# GL3520_4_Ports.net
KiCad netlist of a schematic drawn in Altium Designer
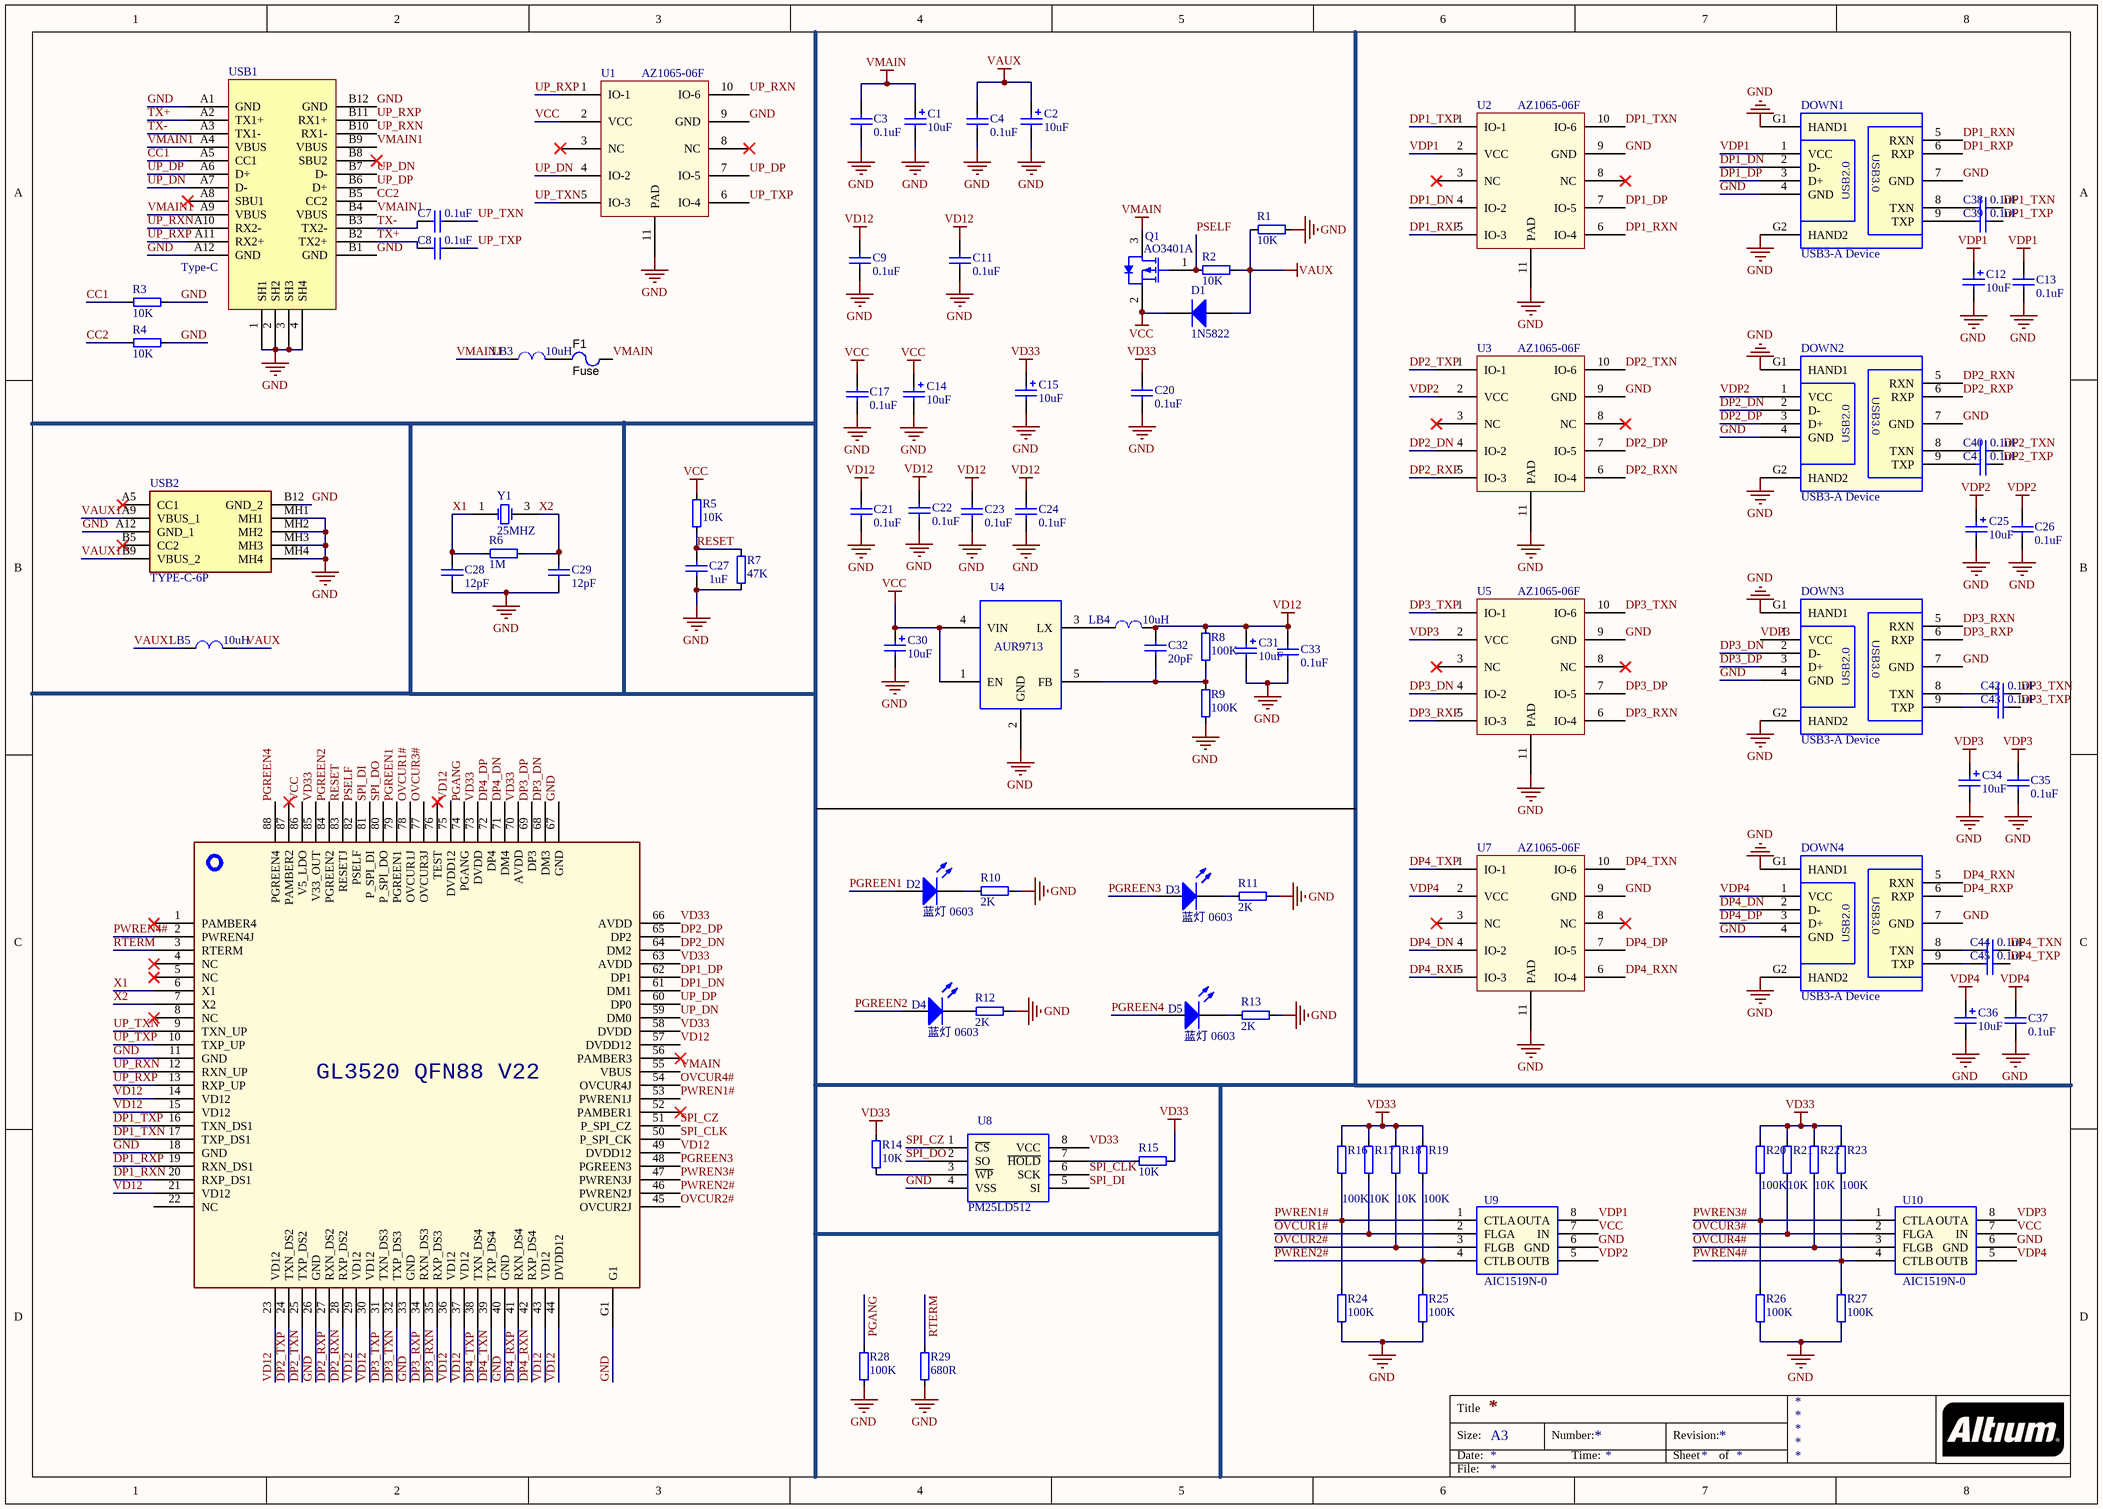
[diagram p0: GL3520 4 Ports.SchDoc]

(export (version "E")
  (design (tool "Eeschema 10.0.6"))
  (components
    (comp (ref "C1")
      (value "10uF")
      (footprint "CASE-A_3216")
      (description "钽电容1206")
      (libsource (lib "嘉立创") (part "3216 10uF (106) 10% 16V"))
    )
    (comp (ref "C2")
      (value "10uF")
      (footprint "CASE-A_3216")
      (description "钽电容1206")
      (libsource (lib "嘉立创") (part "3216 10uF (106) 10% 16V"))
    )
    (comp (ref "C3")
      (value "0.1uF")
      (footprint "C 0603_L")
      (description "贴片电容")
      (libsource (lib "嘉立创") (part "0603 2.2uF (225) 10% 16V"))
    )
    (comp (ref "C4")
      (value "0.1uF")
      (footprint "C 0603_L")
      (description "贴片电容")
      (libsource (lib "嘉立创") (part "0603 2.2uF (225) 10% 16V"))
    )
    (comp (ref "C7")
      (value "0.1uF")
      (footprint "C 0603_L")
      (description "贴片电容")
      (libsource (lib "嘉立创") (part "0603 2.2uF (225) 10% 16V"))
    )
    (comp (ref "C8")
      (value "0.1uF")
      (footprint "C 0603_L")
      (description "贴片电容")
      (libsource (lib "嘉立创") (part "0603 2.2uF (225) 10% 16V"))
    )
    (comp (ref "C9")
      (value "0.1uF")
      (footprint "C 0603_L")
      (description "贴片电容")
      (libsource (lib "嘉立创") (part "0603 2.2uF (225) 10% 16V"))
    )
    (comp (ref "C11")
      (value "0.1uF")
      (footprint "C 0603_L")
      (description "贴片电容")
      (libsource (lib "嘉立创") (part "0603 2.2uF (225) 10% 16V"))
    )
    (comp (ref "C12")
      (value "10uF")
      (footprint "CASE-A_3216")
      (description "钽电容")
      (libsource (lib "嘉立创") (part "3216 10uF (106) 10% 16V"))
    )
    (comp (ref "C13")
      (value "0.1uF")
      (footprint "C 0603_L")
      (description "贴片电容")
      (libsource (lib "嘉立创") (part "0603 2.2uF (225) 10% 16V"))
    )
    (comp (ref "C14")
      (value "10uF")
      (footprint "CASE-A_3216")
      (description "钽电容1206")
      (libsource (lib "嘉立创") (part "3216 10uF (106) 10% 16V"))
    )
    (comp (ref "C15")
      (value "10uF")
      (footprint "CASE-A_3216")
      (description "钽电容1206")
      (libsource (lib "嘉立创") (part "3216 10uF (106) 10% 16V"))
    )
    (comp (ref "C17")
      (value "0.1uF")
      (footprint "C 0603_L")
      (description "贴片电容")
      (libsource (lib "嘉立创") (part "0603 2.2uF (225) 10% 16V"))
    )
    (comp (ref "C20")
      (value "0.1uF")
      (footprint "C 0603_L")
      (description "贴片电容")
      (libsource (lib "嘉立创") (part "0603 2.2uF (225) 10% 16V"))
    )
    (comp (ref "C21")
      (value "0.1uF")
      (footprint "C 0603_L")
      (description "贴片电容")
      (libsource (lib "嘉立创") (part "0603 2.2uF (225) 10% 16V"))
    )
    (comp (ref "C22")
      (value "0.1uF")
      (footprint "C 0603_L")
      (description "贴片电容")
      (libsource (lib "嘉立创") (part "0603 2.2uF (225) 10% 16V"))
    )
    (comp (ref "C23")
      (value "0.1uF")
      (footprint "C 0603_L")
      (description "贴片电容")
      (libsource (lib "嘉立创") (part "0603 2.2uF (225) 10% 16V"))
    )
    (comp (ref "C24")
      (value "0.1uF")
      (footprint "C 0603_L")
      (description "贴片电容")
      (libsource (lib "嘉立创") (part "0603 2.2uF (225) 10% 16V"))
    )
    (comp (ref "C25")
      (value "10uF")
      (footprint "CASE-A_3216")
      (description "钽电容")
      (libsource (lib "嘉立创") (part "3216 10uF (106) 10% 16V"))
    )
    (comp (ref "C26")
      (value "0.1uF")
      (footprint "C 0603_L")
      (description "贴片电容")
      (libsource (lib "嘉立创") (part "0603 2.2uF (225) 10% 16V"))
    )
    (comp (ref "C27")
      (value "1uF")
      (footprint "C 0603_L")
      (description "贴片电容")
      (libsource (lib "嘉立创") (part "0603 2.2uF (225) 10% 16V"))
    )
    (comp (ref "C28")
      (value "12pF")
      (footprint "C 0603_L")
      (description "贴片电容")
      (libsource (lib "嘉立创") (part "0603 2.2uF (225) 10% 16V"))
    )
    (comp (ref "C29")
      (value "12pF")
      (footprint "C 0603_L")
      (description "贴片电容")
      (libsource (lib "嘉立创") (part "0603 2.2uF (225) 10% 16V"))
    )
    (comp (ref "C30")
      (value "10uF")
      (footprint "CASE-A_3216")
      (description "钽电容")
      (libsource (lib "嘉立创") (part "3216 10uF (106) 10% 16V"))
    )
    (comp (ref "C31")
      (value "10uF")
      (footprint "CASE-A_3216")
      (description "钽电容")
      (libsource (lib "嘉立创") (part "3216 10uF (106) 10% 16V"))
    )
    (comp (ref "C32")
      (value "20pF")
      (footprint "C 0603_L")
      (description "贴片电容")
      (libsource (lib "嘉立创") (part "0603 2.2uF (225) 10% 16V"))
    )
    (comp (ref "C33")
      (value "0.1uF")
      (footprint "C 0603_L")
      (description "贴片电容")
      (libsource (lib "嘉立创") (part "0603 2.2uF (225) 10% 16V"))
    )
    (comp (ref "C34")
      (value "10uF")
      (footprint "CASE-A_3216")
      (description "钽电容")
      (libsource (lib "嘉立创") (part "3216 10uF (106) 10% 16V"))
    )
    (comp (ref "C35")
      (value "0.1uF")
      (footprint "C 0603_L")
      (description "贴片电容")
      (libsource (lib "嘉立创") (part "0603 2.2uF (225) 10% 16V"))
    )
    (comp (ref "C36")
      (value "10uF")
      (footprint "CASE-A_3216")
      (description "钽电容")
      (libsource (lib "嘉立创") (part "3216 10uF (106) 10% 16V"))
    )
    (comp (ref "C37")
      (value "0.1uF")
      (footprint "C 0603_L")
      (description "贴片电容")
      (libsource (lib "嘉立创") (part "0603 2.2uF (225) 10% 16V"))
    )
    (comp (ref "C38")
      (value "0.1uF")
      (footprint "C 0603_L")
      (description "贴片电容")
      (libsource (lib "嘉立创") (part "0603 2.2uF (225) 10% 16V"))
    )
    (comp (ref "C39")
      (value "0.1uF")
      (footprint "C 0603_L")
      (description "贴片电容")
      (libsource (lib "嘉立创") (part "0603 2.2uF (225) 10% 16V"))
    )
    (comp (ref "C40")
      (value "0.1uF")
      (footprint "C 0603_L")
      (description "贴片电容")
      (libsource (lib "嘉立创") (part "0603 2.2uF (225) 10% 16V"))
    )
    (comp (ref "C41")
      (value "0.1uF")
      (footprint "C 0603_L")
      (description "贴片电容")
      (libsource (lib "嘉立创") (part "0603 2.2uF (225) 10% 16V"))
    )
    (comp (ref "C42")
      (value "0.1uF")
      (footprint "C 0603_L")
      (description "贴片电容")
      (libsource (lib "嘉立创") (part "0603 2.2uF (225) 10% 16V"))
    )
    (comp (ref "C43")
      (value "0.1uF")
      (footprint "C 0603_L")
      (description "贴片电容")
      (libsource (lib "嘉立创") (part "0603 2.2uF (225) 10% 16V"))
    )
    (comp (ref "C44")
      (value "0.1uF")
      (footprint "C 0603_L")
      (description "贴片电容")
      (libsource (lib "嘉立创") (part "0603 2.2uF (225) 10% 16V"))
    )
    (comp (ref "C45")
      (value "0.1uF")
      (footprint "C 0603_L")
      (description "贴片电容")
      (libsource (lib "嘉立创") (part "0603 2.2uF (225) 10% 16V"))
    )
    (comp (ref "D1")
      (value "1N5822")
      (footprint "SMA")
      (description "3 Amp General Purpose Rectifier")
      (fields (field (name "PUBLISHER") "Altium Limited"))
      (libsource (lib "Miscellaneous Devices") (part "Diode 1N5400"))
    )
    (comp (ref "D2")
      (value "蓝灯 0603")
      (footprint "0603_LED_S1")
      (description "发光二极管")
      (libsource (lib "嘉立创") (part "0603 蓝灯"))
    )
    (comp (ref "D3")
      (value "蓝灯 0603")
      (footprint "0603_LED_S1")
      (description "发光二极管")
      (libsource (lib "嘉立创") (part "0603 蓝灯"))
    )
    (comp (ref "D4")
      (value "蓝灯 0603")
      (footprint "0603_LED_S1")
      (description "发光二极管")
      (libsource (lib "嘉立创") (part "0603 蓝灯"))
    )
    (comp (ref "D5")
      (value "蓝灯 0603")
      (footprint "0603_LED_S1")
      (description "发光二极管")
      (libsource (lib "嘉立创") (part "0603 蓝灯"))
    )
    (comp (ref "DOWN1")
      (value "USB3-A Device")
      (footprint "USB3.0-1 - duplicate")
      (libsource (lib "*") (part "USB3-A_5"))
    )
    (comp (ref "DOWN2")
      (value "USB3-A Device")
      (footprint "USB3.0-1 - duplicate")
      (libsource (lib "*") (part "USB3-A_5"))
    )
    (comp (ref "DOWN3")
      (value "USB3-A Device")
      (footprint "USB3.0-1 - duplicate")
      (libsource (lib "*") (part "USB3-A_5"))
    )
    (comp (ref "DOWN4")
      (value "USB3-A Device")
      (footprint "USB3.0-1 - duplicate")
      (libsource (lib "*") (part "USB3-A_5"))
    )
    (comp (ref "F1")
      (value "Fuse")
      (footprint "FU 1206")
      (fields
        (field (name "PARTNUMBER") "NANOSMDC020F-2")
        (field (name "MANUFACTURER") "TE Connectivity")
        (field (name "PUBLISHER") "Texas Instruments")
        (field (name "SYMBOLCREATOR") "a0412235")
      )
      (libsource (lib "TUSB8041_USB_3.0_Hub") (part "Fuse"))
    )
    (comp (ref "LB3") (value "10uH") (footprint "CD43") (libsource (lib "*") (part "L-0603")))
    (comp (ref "LB4") (value "10uH") (footprint "CD43") (libsource (lib "*") (part "L-0603")))
    (comp (ref "LB5") (value "10uH") (footprint "CD43") (libsource (lib "*") (part "L-0603")))
    (comp (ref "Q1")
      (value "AO3401A")
      (footprint "SOT23-3L")
      (description "P-Channel MOSFET, 30 V, 4 A, -55 to 150 degC, 3-Pin SOT-23-3L, RoHS, Tape and Reel")
      (fields (field (name "MANUFACTURER") "Alpha and Omega"))
      (libsource (lib "GL3520 4 Ports") (part "CMP-2000-05778-1"))
    )
    (comp (ref "R1") (value "10K") (footprint "R 0603_L") (libsource (lib "Jlink OB") (part "RES")))
    (comp (ref "R2") (value "10K") (footprint "R 0603_L") (libsource (lib "Jlink OB") (part "RES")))
    (comp (ref "R3") (value "10K") (footprint "R 0603_L") (libsource (lib "Jlink OB") (part "RES")))
    (comp (ref "R4") (value "10K") (footprint "R 0603_L") (libsource (lib "Jlink OB") (part "RES")))
    (comp (ref "R5") (value "10K") (footprint "R 0603_L") (libsource (lib "Jlink OB") (part "RES")))
    (comp (ref "R6") (value "1M") (footprint "R 0603_L") (libsource (lib "Jlink OB") (part "RES")))
    (comp (ref "R7") (value "47K") (footprint "R 0603_L") (libsource (lib "Jlink OB") (part "RES")))
    (comp (ref "R8") (value "100K") (footprint "R 0603_L") (libsource (lib "Jlink OB") (part "RES")))
    (comp (ref "R9") (value "100K") (footprint "R 0603_L") (libsource (lib "Jlink OB") (part "RES")))
    (comp (ref "R10") (value "2K") (footprint "R 0603_L") (libsource (lib "Jlink OB") (part "RES")))
    (comp (ref "R11") (value "2K") (footprint "R 0603_L") (libsource (lib "Jlink OB") (part "RES")))
    (comp (ref "R12") (value "2K") (footprint "R 0603_L") (libsource (lib "Jlink OB") (part "RES")))
    (comp (ref "R13") (value "2K") (footprint "R 0603_L") (libsource (lib "Jlink OB") (part "RES")))
    (comp (ref "R14") (value "10K") (footprint "R 0603_L") (libsource (lib "Jlink OB") (part "RES")))
    (comp (ref "R15") (value "10K") (footprint "R 0603_L") (libsource (lib "Jlink OB") (part "RES")))
    (comp (ref "R16") (value "100K") (footprint "R 0603_L") (libsource (lib "Jlink OB") (part "RES")))
    (comp (ref "R17") (value "10K") (footprint "R 0603_L") (libsource (lib "Jlink OB") (part "RES")))
    (comp (ref "R18") (value "10K") (footprint "R 0603_L") (libsource (lib "Jlink OB") (part "RES")))
    (comp (ref "R19") (value "100K") (footprint "R 0603_L") (libsource (lib "Jlink OB") (part "RES")))
    (comp (ref "R20") (value "100K") (footprint "R 0603_L") (libsource (lib "Jlink OB") (part "RES")))
    (comp (ref "R21") (value "10K") (footprint "R 0603_L") (libsource (lib "Jlink OB") (part "RES")))
    (comp (ref "R22") (value "10K") (footprint "R 0603_L") (libsource (lib "Jlink OB") (part "RES")))
    (comp (ref "R23") (value "100K") (footprint "R 0603_L") (libsource (lib "Jlink OB") (part "RES")))
    (comp (ref "R24") (value "100K") (footprint "R 0603_L") (libsource (lib "Jlink OB") (part "RES")))
    (comp (ref "R25") (value "100K") (footprint "R 0603_L") (libsource (lib "Jlink OB") (part "RES")))
    (comp (ref "R26") (value "100K") (footprint "R 0603_L") (libsource (lib "Jlink OB") (part "RES")))
    (comp (ref "R27") (value "100K") (footprint "R 0603_L") (libsource (lib "Jlink OB") (part "RES")))
    (comp (ref "R28") (value "100K") (footprint "R 0603_L") (libsource (lib "Jlink OB") (part "RES")))
    (comp (ref "R29") (value "680R") (footprint "R 0603_L") (libsource (lib "Jlink OB") (part "RES")))
    (comp (ref "U1")
      (value "AZ1065-06F")
      (footprint "DFN4120P10E")
      (description "晶炎AZ1065-06F.R7G DFN4120 丝印119 ESD/TVS静电保护二极管")
      (libsource (lib "GL3520 4 Ports") (part "AZ1065-06F"))
    )
    (comp (ref "U2")
      (value "AZ1065-06F")
      (footprint "DFN4120P10E")
      (description "晶炎AZ1065-06F.R7G DFN4120 丝印119 ESD/TVS静电保护二极管")
      (libsource (lib "GL3520 4 Ports") (part "AZ1065-06F"))
    )
    (comp (ref "U3")
      (value "AZ1065-06F")
      (footprint "DFN4120P10E")
      (description "晶炎AZ1065-06F.R7G DFN4120 丝印119 ESD/TVS静电保护二极管")
      (libsource (lib "GL3520 4 Ports") (part "AZ1065-06F"))
    )
    (comp (ref "U4") (value "AUR9713") (footprint "SOT23-5L") (libsource (lib "*") (part "AUR9705_3")))
    (comp (ref "U5")
      (value "AZ1065-06F")
      (footprint "DFN4120P10E")
      (description "晶炎AZ1065-06F.R7G DFN4120 丝印119 ESD/TVS静电保护二极管")
      (libsource (lib "GL3520 4 Ports") (part "AZ1065-06F"))
    )
    (comp (ref "U6")
      (value "GL3520_QFN88_V094-1_22")
      (footprint "QFN88")
      (libsource (lib "GL3520 4 Ports") (part "GL3520_QFN88_V094-1_22"))
    )
    (comp (ref "U7")
      (value "AZ1065-06F")
      (footprint "DFN4120P10E")
      (description "晶炎AZ1065-06F.R7G DFN4120 丝印119 ESD/TVS静电保护二极管")
      (libsource (lib "GL3520 4 Ports") (part "AZ1065-06F"))
    )
    (comp (ref "U8") (value "PM25LD512") (footprint "SOP8W_M") (libsource (lib "*") (part "CAT25C128/256")))
    (comp (ref "U9") (value "AIC1519N-0") (footprint "SOP8_L") (libsource (lib "*") (part "AIC1526-SOP")))
    (comp (ref "U10") (value "AIC1519N-0") (footprint "SOP8_L") (libsource (lib "*") (part "AIC1526-SOP")))
    (comp (ref "USB1")
      (value "Type-C")
      (footprint "USB-C-SMD_U262-241N-4BV60")
      (libsource (lib "Jlink OB") (part "Type-C"))
    )
    (comp (ref "USB2")
      (value "TYPE-C-6P")
      (footprint "TYPE-C-SMD_TYPE-C-31-M-16")
      (description "Connector")
      (fields (field (name "MANUFACTURER_PART_NUMBER") "TYPE-C-31-M-17"))
      (libsource (lib "SamacSys") (part "TYPE-C-31-M-17"))
    )
    (comp (ref "Y1")
      (value "25MHZ")
      (footprint "OSC 3225-4P")
      (description "贴片晶振")
      (libsource (lib "嘉立创") (part "SMD-3225_4P  25MHZ 12PF 10PPM"))
    )
  )
  (nets
    (net (code "1") (name "/CC1") (class "Default")
      (node (ref "R3") (pin "1") (pinfunction "1_1") (pintype "passive"))
      (node (ref "USB1") (pin "A5") (pinfunction "CC1_A5") (pintype "passive"))
    )
    (net (code "2") (name "/CC2") (class "Default")
      (node (ref "R4") (pin "1") (pinfunction "1_1") (pintype "passive"))
      (node (ref "USB1") (pin "B5") (pinfunction "CC2_B5") (pintype "passive"))
    )
    (net (code "3") (name "/DP1_DN") (class "Default")
      (node (ref "DOWN1") (pin "2") (pinfunction "D-_2") (pintype "passive"))
      (node (ref "U2") (pin "4") (pinfunction "IO-2_4") (pintype "passive"))
      (node (ref "U6") (pin "61") (pinfunction "DM1_61") (pintype "passive"))
    )
    (net (code "4") (name "/DP1_DP") (class "Default")
      (node (ref "DOWN1") (pin "3") (pinfunction "D+_3") (pintype "passive"))
      (node (ref "U2") (pin "7") (pinfunction "IO-5_7") (pintype "passive"))
      (node (ref "U6") (pin "62") (pinfunction "DP1_62") (pintype "passive"))
    )
    (net (code "5") (name "/DP1_RXN") (class "Default")
      (node (ref "DOWN1") (pin "5") (pinfunction "RXN_5") (pintype "passive"))
      (node (ref "U2") (pin "6") (pinfunction "IO-4_6") (pintype "passive"))
      (node (ref "U6") (pin "20") (pinfunction "RXP_DS1_20") (pintype "passive"))
    )
    (net (code "6") (name "/DP1_RXP") (class "Default")
      (node (ref "DOWN1") (pin "6") (pinfunction "RXP_6") (pintype "passive"))
      (node (ref "U2") (pin "5") (pinfunction "IO-3_5") (pintype "passive"))
      (node (ref "U6") (pin "19") (pinfunction "RXN_DS1_19") (pintype "passive"))
    )
    (net (code "7") (name "/DP1_TXN") (class "Default")
      (node (ref "C38") (pin "1") (pinfunction "1_1") (pintype "passive"))
      (node (ref "U2") (pin "10") (pinfunction "IO-6_10") (pintype "passive"))
      (node (ref "U6") (pin "17") (pinfunction "TXP_DS1_17") (pintype "passive"))
    )
    (net (code "8") (name "/DP1_TXP") (class "Default")
      (node (ref "C39") (pin "1") (pinfunction "1_1") (pintype "passive"))
      (node (ref "U2") (pin "1") (pinfunction "IO-1_1") (pintype "passive"))
      (node (ref "U6") (pin "16") (pinfunction "TXN_DS1_16") (pintype "passive"))
    )
    (net (code "9") (name "/DP2_DN") (class "Default")
      (node (ref "DOWN2") (pin "2") (pinfunction "D-_2") (pintype "passive"))
      (node (ref "U3") (pin "4") (pinfunction "IO-2_4") (pintype "passive"))
      (node (ref "U6") (pin "64") (pinfunction "DM2_64") (pintype "passive"))
    )
    (net (code "10") (name "/DP2_DP") (class "Default")
      (node (ref "DOWN2") (pin "3") (pinfunction "D+_3") (pintype "passive"))
      (node (ref "U3") (pin "7") (pinfunction "IO-5_7") (pintype "passive"))
      (node (ref "U6") (pin "65") (pinfunction "DP2_65") (pintype "passive"))
    )
    (net (code "11") (name "/DP2_RXN") (class "Default")
      (node (ref "DOWN2") (pin "5") (pinfunction "RXN_5") (pintype "passive"))
      (node (ref "U3") (pin "6") (pinfunction "IO-4_6") (pintype "passive"))
      (node (ref "U6") (pin "28") (pinfunction "RXP_DS2_28") (pintype "passive"))
    )
    (net (code "12") (name "/DP2_RXP") (class "Default")
      (node (ref "DOWN2") (pin "6") (pinfunction "RXP_6") (pintype "passive"))
      (node (ref "U3") (pin "5") (pinfunction "IO-3_5") (pintype "passive"))
      (node (ref "U6") (pin "27") (pinfunction "RXN_DS2_27") (pintype "passive"))
    )
    (net (code "13") (name "/DP2_TXN") (class "Default")
      (node (ref "C40") (pin "1") (pinfunction "1_1") (pintype "passive"))
      (node (ref "U3") (pin "10") (pinfunction "IO-6_10") (pintype "passive"))
      (node (ref "U6") (pin "25") (pinfunction "TXP_DS2_25") (pintype "passive"))
    )
    (net (code "14") (name "/DP2_TXP") (class "Default")
      (node (ref "C41") (pin "1") (pinfunction "1_1") (pintype "passive"))
      (node (ref "U3") (pin "1") (pinfunction "IO-1_1") (pintype "passive"))
      (node (ref "U6") (pin "24") (pinfunction "TXN_DS2_24") (pintype "passive"))
    )
    (net (code "15") (name "/DP3_DN") (class "Default")
      (node (ref "DOWN3") (pin "2") (pinfunction "D-_2") (pintype "passive"))
      (node (ref "U5") (pin "4") (pinfunction "IO-2_4") (pintype "passive"))
      (node (ref "U6") (pin "68") (pinfunction "DM3_68") (pintype "passive"))
    )
    (net (code "16") (name "/DP3_DP") (class "Default")
      (node (ref "DOWN3") (pin "3") (pinfunction "D+_3") (pintype "passive"))
      (node (ref "U5") (pin "7") (pinfunction "IO-5_7") (pintype "passive"))
      (node (ref "U6") (pin "69") (pinfunction "DP3_69") (pintype "passive"))
    )
    (net (code "17") (name "/DP3_RXN") (class "Default")
      (node (ref "DOWN3") (pin "5") (pinfunction "RXN_5") (pintype "passive"))
      (node (ref "U5") (pin "6") (pinfunction "IO-4_6") (pintype "passive"))
      (node (ref "U6") (pin "35") (pinfunction "RXP_DS3_35") (pintype "passive"))
    )
    (net (code "18") (name "/DP3_RXP") (class "Default")
      (node (ref "DOWN3") (pin "6") (pinfunction "RXP_6") (pintype "passive"))
      (node (ref "U5") (pin "5") (pinfunction "IO-3_5") (pintype "passive"))
      (node (ref "U6") (pin "34") (pinfunction "RXN_DS3_34") (pintype "passive"))
    )
    (net (code "19") (name "/DP3_TXN") (class "Default")
      (node (ref "C42") (pin "1") (pinfunction "1_1") (pintype "passive"))
      (node (ref "U5") (pin "10") (pinfunction "IO-6_10") (pintype "passive"))
      (node (ref "U6") (pin "32") (pinfunction "TXP_DS3_32") (pintype "passive"))
    )
    (net (code "20") (name "/DP3_TXP") (class "Default")
      (node (ref "C43") (pin "1") (pinfunction "1_1") (pintype "passive"))
      (node (ref "U5") (pin "1") (pinfunction "IO-1_1") (pintype "passive"))
      (node (ref "U6") (pin "31") (pinfunction "TXN_DS3_31") (pintype "passive"))
    )
    (net (code "21") (name "/DP4_DN") (class "Default")
      (node (ref "DOWN4") (pin "2") (pinfunction "D-_2") (pintype "passive"))
      (node (ref "U6") (pin "71") (pinfunction "DM4_71") (pintype "passive"))
      (node (ref "U7") (pin "4") (pinfunction "IO-2_4") (pintype "passive"))
    )
    (net (code "22") (name "/DP4_DP") (class "Default")
      (node (ref "DOWN4") (pin "3") (pinfunction "D+_3") (pintype "passive"))
      (node (ref "U6") (pin "72") (pinfunction "DP4_72") (pintype "passive"))
      (node (ref "U7") (pin "7") (pinfunction "IO-5_7") (pintype "passive"))
    )
    (net (code "23") (name "/DP4_RXN") (class "Default")
      (node (ref "DOWN4") (pin "5") (pinfunction "RXN_5") (pintype "passive"))
      (node (ref "U6") (pin "42") (pinfunction "RXP_DS4_42") (pintype "passive"))
      (node (ref "U7") (pin "6") (pinfunction "IO-4_6") (pintype "passive"))
    )
    (net (code "24") (name "/DP4_RXP") (class "Default")
      (node (ref "DOWN4") (pin "6") (pinfunction "RXP_6") (pintype "passive"))
      (node (ref "U6") (pin "41") (pinfunction "RXN_DS4_41") (pintype "passive"))
      (node (ref "U7") (pin "5") (pinfunction "IO-3_5") (pintype "passive"))
    )
    (net (code "25") (name "/DP4_TXN") (class "Default")
      (node (ref "C44") (pin "1") (pinfunction "1_1") (pintype "passive"))
      (node (ref "U6") (pin "39") (pinfunction "TXP_DS4_39") (pintype "passive"))
      (node (ref "U7") (pin "10") (pinfunction "IO-6_10") (pintype "passive"))
    )
    (net (code "26") (name "/DP4_TXP") (class "Default")
      (node (ref "C45") (pin "1") (pinfunction "1_1") (pintype "passive"))
      (node (ref "U6") (pin "38") (pinfunction "TXN_DS4_38") (pintype "passive"))
      (node (ref "U7") (pin "1") (pinfunction "IO-1_1") (pintype "passive"))
    )
    (net (code "27") (name "/OVCUR1#") (class "Default")
      (node (ref "R17") (pin "2") (pinfunction "2_2") (pintype "passive"))
      (node (ref "U6") (pin "78") (pinfunction "OVCUR1J_78") (pintype "passive"))
      (node (ref "U9") (pin "2") (pinfunction "FLGA_2") (pintype "passive"))
    )
    (net (code "28") (name "/OVCUR2#") (class "Default")
      (node (ref "R18") (pin "2") (pinfunction "2_2") (pintype "passive"))
      (node (ref "U6") (pin "45") (pinfunction "OVCUR2J_45") (pintype "passive"))
      (node (ref "U9") (pin "3") (pinfunction "FLGB_3") (pintype "passive"))
    )
    (net (code "29") (name "/OVCUR3#") (class "Default")
      (node (ref "R21") (pin "2") (pinfunction "2_2") (pintype "passive"))
      (node (ref "U10") (pin "2") (pinfunction "FLGA_2") (pintype "passive"))
      (node (ref "U6") (pin "77") (pinfunction "OVCUR3J_77") (pintype "passive"))
    )
    (net (code "30") (name "/OVCUR4#") (class "Default")
      (node (ref "R22") (pin "2") (pinfunction "2_2") (pintype "passive"))
      (node (ref "U10") (pin "3") (pinfunction "FLGB_3") (pintype "passive"))
      (node (ref "U6") (pin "54") (pinfunction "OVCUR4J_54") (pintype "passive"))
    )
    (net (code "31") (name "/PGANG") (class "Default")
      (node (ref "R28") (pin "1") (pinfunction "1_1") (pintype "passive"))
      (node (ref "U6") (pin "74") (pinfunction "PGANG_74") (pintype "passive"))
    )
    (net (code "32") (name "/PGREEN1") (class "Default")
      (node (ref "D2") (pin "A") (pinfunction "A_A") (pintype "passive"))
      (node (ref "U6") (pin "79") (pinfunction "PGREEN1_79") (pintype "passive"))
    )
    (net (code "33") (name "/PGREEN2") (class "Default")
      (node (ref "D4") (pin "A") (pinfunction "A_A") (pintype "passive"))
      (node (ref "U6") (pin "84") (pinfunction "PGREEN2_84") (pintype "passive"))
    )
    (net (code "34") (name "/PGREEN3") (class "Default")
      (node (ref "D3") (pin "A") (pinfunction "A_A") (pintype "passive"))
      (node (ref "U6") (pin "48") (pinfunction "PGREEN3_48") (pintype "passive"))
    )
    (net (code "35") (name "/PGREEN4") (class "Default")
      (node (ref "D5") (pin "A") (pinfunction "A_A") (pintype "passive"))
      (node (ref "U6") (pin "88") (pinfunction "PGREEN4_88") (pintype "passive"))
    )
    (net (code "36") (name "/PSELF") (class "Default")
      (node (ref "Q1") (pin "1") (pinfunction "GATE_1") (pintype "passive"))
      (node (ref "R2") (pin "1") (pinfunction "1_1") (pintype "passive"))
      (node (ref "U6") (pin "82") (pinfunction "PSELF_82") (pintype "passive"))
    )
    (net (code "37") (name "/PWREN1#") (class "Default")
      (node (ref "R16") (pin "2") (pinfunction "2_2") (pintype "passive"))
      (node (ref "R24") (pin "1") (pinfunction "1_1") (pintype "passive"))
      (node (ref "U6") (pin "53") (pinfunction "PWREN1J_53") (pintype "passive"))
      (node (ref "U9") (pin "1") (pinfunction "CTLA_1") (pintype "passive"))
    )
    (net (code "38") (name "/PWREN2#") (class "Default")
      (node (ref "R19") (pin "2") (pinfunction "2_2") (pintype "passive"))
      (node (ref "R25") (pin "1") (pinfunction "1_1") (pintype "passive"))
      (node (ref "U6") (pin "46") (pinfunction "PWREN2J_46") (pintype "passive"))
      (node (ref "U9") (pin "4") (pinfunction "CTLB_4") (pintype "passive"))
    )
    (net (code "39") (name "/PWREN3#") (class "Default")
      (node (ref "R20") (pin "2") (pinfunction "2_2") (pintype "passive"))
      (node (ref "R26") (pin "1") (pinfunction "1_1") (pintype "passive"))
      (node (ref "U10") (pin "1") (pinfunction "CTLA_1") (pintype "passive"))
      (node (ref "U6") (pin "47") (pinfunction "PWREN3J_47") (pintype "passive"))
    )
    (net (code "40") (name "/PWREN4#") (class "Default")
      (node (ref "R23") (pin "2") (pinfunction "2_2") (pintype "passive"))
      (node (ref "R27") (pin "1") (pinfunction "1_1") (pintype "passive"))
      (node (ref "U10") (pin "4") (pinfunction "CTLB_4") (pintype "passive"))
      (node (ref "U6") (pin "2") (pinfunction "PWREN4J_2") (pintype "passive"))
    )
    (net (code "41") (name "/RESET") (class "Default")
      (node (ref "C27") (pin "2") (pinfunction "2_2") (pintype "passive"))
      (node (ref "R5") (pin "1") (pinfunction "1_1") (pintype "passive"))
      (node (ref "R7") (pin "2") (pinfunction "2_2") (pintype "passive"))
      (node (ref "U6") (pin "83") (pinfunction "RESETJ_83") (pintype "passive"))
    )
    (net (code "42") (name "/RTERM") (class "Default")
      (node (ref "R29") (pin "1") (pinfunction "1_1") (pintype "passive"))
      (node (ref "U6") (pin "3") (pinfunction "RTERM_3") (pintype "passive"))
    )
    (net (code "43") (name "/SPI_CLK") (class "Default")
      (node (ref "U6") (pin "50") (pinfunction "P_SPI_CK_50") (pintype "passive"))
      (node (ref "U8") (pin "6") (pinfunction "SCK_6") (pintype "passive"))
    )
    (net (code "44") (name "/SPI_CZ") (class "Default")
      (node (ref "U6") (pin "51") (pinfunction "P_SPI_CZ_51") (pintype "passive"))
      (node (ref "U8") (pin "1") (pinfunction "~{CS}_1") (pintype "passive"))
    )
    (net (code "45") (name "/SPI_DI") (class "Default")
      (node (ref "U6") (pin "81") (pinfunction "P_SPI_DI_81") (pintype "passive"))
      (node (ref "U8") (pin "5") (pinfunction "SI_5") (pintype "passive"))
    )
    (net (code "46") (name "/SPI_DO") (class "Default")
      (node (ref "U6") (pin "80") (pinfunction "P_SPI_DO_80") (pintype "passive"))
      (node (ref "U8") (pin "2") (pinfunction "SO_2") (pintype "passive"))
    )
    (net (code "47") (name "/TX+") (class "Default")
      (node (ref "C8") (pin "2") (pinfunction "2_2") (pintype "passive"))
      (node (ref "USB1") (pin "A2") (pinfunction "TX1+_A2") (pintype "passive"))
      (node (ref "USB1") (pin "B2") (pinfunction "TX2+_B2") (pintype "passive"))
    )
    (net (code "48") (name "/TX-") (class "Default")
      (node (ref "C7") (pin "2") (pinfunction "2_2") (pintype "passive"))
      (node (ref "USB1") (pin "A3") (pinfunction "TX1-_A3") (pintype "passive"))
      (node (ref "USB1") (pin "B3") (pinfunction "TX2-_B3") (pintype "passive"))
    )
    (net (code "49") (name "/UP_DN") (class "Default")
      (node (ref "U1") (pin "4") (pinfunction "IO-2_4") (pintype "passive"))
      (node (ref "U6") (pin "59") (pinfunction "DM0_59") (pintype "passive"))
      (node (ref "USB1") (pin "A7") (pinfunction "D-_A7") (pintype "passive"))
      (node (ref "USB1") (pin "B7") (pinfunction "D-_B7") (pintype "passive"))
    )
    (net (code "50") (name "/UP_DP") (class "Default")
      (node (ref "U1") (pin "7") (pinfunction "IO-5_7") (pintype "passive"))
      (node (ref "U6") (pin "60") (pinfunction "DP0_60") (pintype "passive"))
      (node (ref "USB1") (pin "A6") (pinfunction "D+_A6") (pintype "passive"))
      (node (ref "USB1") (pin "B6") (pinfunction "D+_B6") (pintype "passive"))
    )
    (net (code "51") (name "/UP_RXN") (class "Default")
      (node (ref "U1") (pin "10") (pinfunction "IO-6_10") (pintype "passive"))
      (node (ref "U6") (pin "12") (pinfunction "RXN_UP_12") (pintype "passive"))
      (node (ref "USB1") (pin "A10") (pinfunction "RX2-_A10") (pintype "passive"))
      (node (ref "USB1") (pin "B10") (pinfunction "RX1-_B10") (pintype "passive"))
    )
    (net (code "52") (name "/UP_RXP") (class "Default")
      (node (ref "U1") (pin "1") (pinfunction "IO-1_1") (pintype "passive"))
      (node (ref "U6") (pin "13") (pinfunction "RXP_UP_13") (pintype "passive"))
      (node (ref "USB1") (pin "A11") (pinfunction "RX2+_A11") (pintype "passive"))
      (node (ref "USB1") (pin "B11") (pinfunction "RX1+_B11") (pintype "passive"))
    )
    (net (code "53") (name "/UP_TXN") (class "Default")
      (node (ref "C7") (pin "1") (pinfunction "1_1") (pintype "passive"))
      (node (ref "U1") (pin "5") (pinfunction "IO-3_5") (pintype "passive"))
      (node (ref "U6") (pin "9") (pinfunction "TXN_UP_9") (pintype "passive"))
    )
    (net (code "54") (name "/UP_TXP") (class "Default")
      (node (ref "C8") (pin "1") (pinfunction "1_1") (pintype "passive"))
      (node (ref "U1") (pin "6") (pinfunction "IO-4_6") (pintype "passive"))
      (node (ref "U6") (pin "10") (pinfunction "TXP_UP_10") (pintype "passive"))
    )
    (net (code "55") (name "/VAUX1") (class "Default")
      (node (ref "LB5") (pin "1") (pinfunction "1_1") (pintype "passive"))
      (node (ref "USB2") (pin "A9") (pinfunction "VBUS_1_A9") (pintype "passive"))
      (node (ref "USB2") (pin "B9") (pinfunction "VBUS_2_B9") (pintype "passive"))
    )
    (net (code "56") (name "/VMAIN1") (class "Default")
      (node (ref "LB3") (pin "1") (pinfunction "1_1") (pintype "passive"))
      (node (ref "USB1") (pin "A4") (pinfunction "VBUS_A4") (pintype "passive"))
      (node (ref "USB1") (pin "A9") (pinfunction "VBUS_A9") (pintype "passive"))
      (node (ref "USB1") (pin "B4") (pinfunction "VBUS_B4") (pintype "passive"))
      (node (ref "USB1") (pin "B9") (pinfunction "VBUS_B9") (pintype "passive"))
    )
    (net (code "57") (name "/X1") (class "Default")
      (node (ref "C28") (pin "2") (pinfunction "2_2") (pintype "passive"))
      (node (ref "R6") (pin "1") (pinfunction "1_1") (pintype "passive"))
      (node (ref "U6") (pin "6") (pinfunction "X1_6") (pintype "passive"))
      (node (ref "Y1") (pin "1") (pinfunction "OSC1_1") (pintype "passive"))
    )
    (net (code "58") (name "/X2") (class "Default")
      (node (ref "C29") (pin "2") (pinfunction "2_2") (pintype "passive"))
      (node (ref "R6") (pin "2") (pinfunction "2_2") (pintype "passive"))
      (node (ref "U6") (pin "7") (pinfunction "X2_7") (pintype "passive"))
      (node (ref "Y1") (pin "3") (pinfunction "OSC2_3") (pintype "passive"))
    )
    (net (code "59") (name "GND") (class "Default")
      (node (ref "C1") (pin "2") (pinfunction "2_2") (pintype "passive"))
      (node (ref "C11") (pin "1") (pinfunction "1_1") (pintype "passive"))
      (node (ref "C12") (pin "2") (pinfunction "2_2") (pintype "passive"))
      (node (ref "C13") (pin "1") (pinfunction "1_1") (pintype "passive"))
      (node (ref "C14") (pin "2") (pinfunction "2_2") (pintype "passive"))
      (node (ref "C15") (pin "2") (pinfunction "2_2") (pintype "passive"))
      (node (ref "C17") (pin "1") (pinfunction "1_1") (pintype "passive"))
      (node (ref "C2") (pin "2") (pinfunction "2_2") (pintype "passive"))
      (node (ref "C20") (pin "1") (pinfunction "1_1") (pintype "passive"))
      (node (ref "C21") (pin "1") (pinfunction "1_1") (pintype "passive"))
      (node (ref "C22") (pin "1") (pinfunction "1_1") (pintype "passive"))
      (node (ref "C23") (pin "1") (pinfunction "1_1") (pintype "passive"))
      (node (ref "C24") (pin "1") (pinfunction "1_1") (pintype "passive"))
      (node (ref "C25") (pin "2") (pinfunction "2_2") (pintype "passive"))
      (node (ref "C26") (pin "1") (pinfunction "1_1") (pintype "passive"))
      (node (ref "C27") (pin "1") (pinfunction "1_1") (pintype "passive"))
      (node (ref "C28") (pin "1") (pinfunction "1_1") (pintype "passive"))
      (node (ref "C29") (pin "1") (pinfunction "1_1") (pintype "passive"))
      (node (ref "C3") (pin "1") (pinfunction "1_1") (pintype "passive"))
      (node (ref "C30") (pin "2") (pinfunction "2_2") (pintype "passive"))
      (node (ref "C31") (pin "2") (pinfunction "2_2") (pintype "passive"))
      (node (ref "C33") (pin "1") (pinfunction "1_1") (pintype "passive"))
      (node (ref "C34") (pin "2") (pinfunction "2_2") (pintype "passive"))
      (node (ref "C35") (pin "1") (pinfunction "1_1") (pintype "passive"))
      (node (ref "C36") (pin "2") (pinfunction "2_2") (pintype "passive"))
      (node (ref "C37") (pin "1") (pinfunction "1_1") (pintype "passive"))
      (node (ref "C4") (pin "1") (pinfunction "1_1") (pintype "passive"))
      (node (ref "C9") (pin "1") (pinfunction "1_1") (pintype "passive"))
      (node (ref "DOWN1") (pin "4") (pinfunction "GND_4") (pintype "power_in"))
      (node (ref "DOWN1") (pin "7") (pinfunction "GND_7") (pintype "power_in"))
      (node (ref "DOWN1") (pin "G1") (pinfunction "HAND1_G1") (pintype "passive"))
      (node (ref "DOWN1") (pin "G2") (pinfunction "HAND2_G2") (pintype "passive"))
      (node (ref "DOWN2") (pin "4") (pinfunction "GND_4") (pintype "power_in"))
      (node (ref "DOWN2") (pin "7") (pinfunction "GND_7") (pintype "power_in"))
      (node (ref "DOWN2") (pin "G1") (pinfunction "HAND1_G1") (pintype "passive"))
      (node (ref "DOWN2") (pin "G2") (pinfunction "HAND2_G2") (pintype "passive"))
      (node (ref "DOWN3") (pin "4") (pinfunction "GND_4") (pintype "power_in"))
      (node (ref "DOWN3") (pin "7") (pinfunction "GND_7") (pintype "power_in"))
      (node (ref "DOWN3") (pin "G1") (pinfunction "HAND1_G1") (pintype "passive"))
      (node (ref "DOWN3") (pin "G2") (pinfunction "HAND2_G2") (pintype "passive"))
      (node (ref "DOWN4") (pin "4") (pinfunction "GND_4") (pintype "power_in"))
      (node (ref "DOWN4") (pin "7") (pinfunction "GND_7") (pintype "power_in"))
      (node (ref "DOWN4") (pin "G1") (pinfunction "HAND1_G1") (pintype "passive"))
      (node (ref "DOWN4") (pin "G2") (pinfunction "HAND2_G2") (pintype "passive"))
      (node (ref "R1") (pin "2") (pinfunction "2_2") (pintype "passive"))
      (node (ref "R10") (pin "1") (pinfunction "1_1") (pintype "passive"))
      (node (ref "R11") (pin "1") (pinfunction "1_1") (pintype "passive"))
      (node (ref "R12") (pin "1") (pinfunction "1_1") (pintype "passive"))
      (node (ref "R13") (pin "1") (pinfunction "1_1") (pintype "passive"))
      (node (ref "R24") (pin "2") (pinfunction "2_2") (pintype "passive"))
      (node (ref "R25") (pin "2") (pinfunction "2_2") (pintype "passive"))
      (node (ref "R26") (pin "2") (pinfunction "2_2") (pintype "passive"))
      (node (ref "R27") (pin "2") (pinfunction "2_2") (pintype "passive"))
      (node (ref "R28") (pin "2") (pinfunction "2_2") (pintype "passive"))
      (node (ref "R29") (pin "2") (pinfunction "2_2") (pintype "passive"))
      (node (ref "R3") (pin "2") (pinfunction "2_2") (pintype "passive"))
      (node (ref "R4") (pin "2") (pinfunction "2_2") (pintype "passive"))
      (node (ref "R7") (pin "1") (pinfunction "1_1") (pintype "passive"))
      (node (ref "R9") (pin "2") (pinfunction "2_2") (pintype "passive"))
      (node (ref "U1") (pin "11") (pinfunction "PAD_11") (pintype "passive"))
      (node (ref "U1") (pin "9") (pinfunction "GND_9") (pintype "passive"))
      (node (ref "U10") (pin "6") (pinfunction "GND_6") (pintype "passive"))
      (node (ref "U2") (pin "11") (pinfunction "PAD_11") (pintype "passive"))
      (node (ref "U2") (pin "9") (pinfunction "GND_9") (pintype "passive"))
      (node (ref "U3") (pin "11") (pinfunction "PAD_11") (pintype "passive"))
      (node (ref "U3") (pin "9") (pinfunction "GND_9") (pintype "passive"))
      (node (ref "U4") (pin "2") (pinfunction "GND_2") (pintype "passive"))
      (node (ref "U5") (pin "11") (pinfunction "PAD_11") (pintype "passive"))
      (node (ref "U5") (pin "9") (pinfunction "GND_9") (pintype "passive"))
      (node (ref "U6") (pin "11") (pinfunction "GND_11") (pintype "passive"))
      (node (ref "U6") (pin "18") (pinfunction "GND_18") (pintype "passive"))
      (node (ref "U6") (pin "26") (pinfunction "GND_26") (pintype "passive"))
      (node (ref "U6") (pin "33") (pinfunction "GND_33") (pintype "passive"))
      (node (ref "U6") (pin "40") (pinfunction "GND_40") (pintype "passive"))
      (node (ref "U6") (pin "67") (pinfunction "GND_67") (pintype "passive"))
      (node (ref "U6") (pin "G1") (pinfunction "G1_G1") (pintype "passive"))
      (node (ref "U7") (pin "11") (pinfunction "PAD_11") (pintype "passive"))
      (node (ref "U7") (pin "9") (pinfunction "GND_9") (pintype "passive"))
      (node (ref "U8") (pin "4") (pinfunction "VSS_4") (pintype "passive"))
      (node (ref "U9") (pin "6") (pinfunction "GND_6") (pintype "passive"))
      (node (ref "USB1") (pin "1") (pinfunction "SH1_1") (pintype "passive"))
      (node (ref "USB1") (pin "2") (pinfunction "SH2_2") (pintype "passive"))
      (node (ref "USB1") (pin "3") (pinfunction "SH3_3") (pintype "passive"))
      (node (ref "USB1") (pin "4") (pinfunction "SH4_4") (pintype "passive"))
      (node (ref "USB1") (pin "A1") (pinfunction "GND_A1") (pintype "passive"))
      (node (ref "USB1") (pin "A12") (pinfunction "GND_A12") (pintype "passive"))
      (node (ref "USB1") (pin "B1") (pinfunction "GND_B1") (pintype "passive"))
      (node (ref "USB1") (pin "B12") (pinfunction "GND_B12") (pintype "passive"))
      (node (ref "USB2") (pin "A12") (pinfunction "GND_1_A12") (pintype "passive"))
      (node (ref "USB2") (pin "B12") (pinfunction "GND_2_B12") (pintype "passive"))
      (node (ref "USB2") (pin "MH1") (pinfunction "MH1_MH1") (pintype "passive"))
      (node (ref "USB2") (pin "MH2") (pinfunction "MH2_MH2") (pintype "passive"))
      (node (ref "USB2") (pin "MH3") (pinfunction "MH3_MH3") (pintype "passive"))
      (node (ref "USB2") (pin "MH4") (pinfunction "MH4_MH4") (pintype "passive"))
    )
    (net (code "60") (name "Net-(D2-PadK)") (class "Default")
      (node (ref "D2") (pin "K") (pinfunction "K_K") (pintype "passive"))
      (node (ref "R10") (pin "2") (pinfunction "2_2") (pintype "passive"))
    )
    (net (code "61") (name "Net-(D3-PadK)") (class "Default")
      (node (ref "D3") (pin "K") (pinfunction "K_K") (pintype "passive"))
      (node (ref "R11") (pin "2") (pinfunction "2_2") (pintype "passive"))
    )
    (net (code "62") (name "Net-(D4-PadK)") (class "Default")
      (node (ref "D4") (pin "K") (pinfunction "K_K") (pintype "passive"))
      (node (ref "R12") (pin "2") (pinfunction "2_2") (pintype "passive"))
    )
    (net (code "63") (name "Net-(D5-PadK)") (class "Default")
      (node (ref "D5") (pin "K") (pinfunction "K_K") (pintype "passive"))
      (node (ref "R13") (pin "2") (pinfunction "2_2") (pintype "passive"))
    )
    (net (code "64") (name "Net-(DOWN1-TXN)") (class "Default")
      (node (ref "C38") (pin "2") (pinfunction "2_2") (pintype "passive"))
      (node (ref "DOWN1") (pin "8") (pinfunction "TXN_8") (pintype "passive"))
    )
    (net (code "65") (name "Net-(DOWN1-TXP)") (class "Default")
      (node (ref "C39") (pin "2") (pinfunction "2_2") (pintype "passive"))
      (node (ref "DOWN1") (pin "9") (pinfunction "TXP_9") (pintype "passive"))
    )
    (net (code "66") (name "Net-(DOWN2-TXN)") (class "Default")
      (node (ref "C40") (pin "2") (pinfunction "2_2") (pintype "passive"))
      (node (ref "DOWN2") (pin "8") (pinfunction "TXN_8") (pintype "passive"))
    )
    (net (code "67") (name "Net-(DOWN2-TXP)") (class "Default")
      (node (ref "C41") (pin "2") (pinfunction "2_2") (pintype "passive"))
      (node (ref "DOWN2") (pin "9") (pinfunction "TXP_9") (pintype "passive"))
    )
    (net (code "68") (name "Net-(DOWN3-TXN)") (class "Default")
      (node (ref "C42") (pin "2") (pinfunction "2_2") (pintype "passive"))
      (node (ref "DOWN3") (pin "8") (pinfunction "TXN_8") (pintype "passive"))
    )
    (net (code "69") (name "Net-(DOWN3-TXP)") (class "Default")
      (node (ref "C43") (pin "2") (pinfunction "2_2") (pintype "passive"))
      (node (ref "DOWN3") (pin "9") (pinfunction "TXP_9") (pintype "passive"))
    )
    (net (code "70") (name "Net-(DOWN4-TXN)") (class "Default")
      (node (ref "C44") (pin "2") (pinfunction "2_2") (pintype "passive"))
      (node (ref "DOWN4") (pin "8") (pinfunction "TXN_8") (pintype "passive"))
    )
    (net (code "71") (name "Net-(DOWN4-TXP)") (class "Default")
      (node (ref "C45") (pin "2") (pinfunction "2_2") (pintype "passive"))
      (node (ref "DOWN4") (pin "9") (pinfunction "TXP_9") (pintype "passive"))
    )
    (net (code "72") (name "Net-(F1-Pad2)") (class "Default")
      (node (ref "F1") (pin "2") (pinfunction "2_2") (pintype "passive"))
      (node (ref "LB3") (pin "2") (pinfunction "2_2") (pintype "passive"))
    )
    (net (code "73") (name "Net-(U4-FB)") (class "Default")
      (node (ref "C32") (pin "1") (pinfunction "1_1") (pintype "passive"))
      (node (ref "R8") (pin "2") (pinfunction "2_2") (pintype "passive"))
      (node (ref "R9") (pin "1") (pinfunction "1_1") (pintype "passive"))
      (node (ref "U4") (pin "5") (pinfunction "FB_5") (pintype "passive"))
    )
    (net (code "74") (name "Net-(U4-LX)") (class "Default")
      (node (ref "LB4") (pin "1") (pinfunction "1_1") (pintype "passive"))
      (node (ref "U4") (pin "3") (pinfunction "LX_3") (pintype "passive"))
    )
    (net (code "75") (name "Net-(U8-~{HOLD})") (class "Default")
      (node (ref "R15") (pin "1") (pinfunction "1_1") (pintype "passive"))
      (node (ref "U8") (pin "7") (pinfunction "~{HOLD}_7") (pintype "passive"))
    )
    (net (code "76") (name "Net-(U8-~{WP})") (class "Default")
      (node (ref "R14") (pin "2") (pinfunction "2_2") (pintype "passive"))
      (node (ref "U8") (pin "3") (pinfunction "~{WP}_3") (pintype "passive"))
    )
    (net (code "77") (name "VAUX") (class "Default")
      (node (ref "C2") (pin "1") (pinfunction "1_1") (pintype "passive"))
      (node (ref "C4") (pin "2") (pinfunction "2_2") (pintype "passive"))
      (node (ref "D1") (pin "1") (pinfunction "A_1") (pintype "passive"))
      (node (ref "LB5") (pin "2") (pinfunction "2_2") (pintype "passive"))
      (node (ref "R1") (pin "1") (pinfunction "1_1") (pintype "passive"))
      (node (ref "R2") (pin "2") (pinfunction "2_2") (pintype "passive"))
    )
    (net (code "78") (name "VCC") (class "Default")
      (node (ref "C14") (pin "1") (pinfunction "1_1") (pintype "passive"))
      (node (ref "C17") (pin "2") (pinfunction "2_2") (pintype "passive"))
      (node (ref "C30") (pin "1") (pinfunction "1_1") (pintype "passive"))
      (node (ref "D1") (pin "2") (pinfunction "K_2") (pintype "passive"))
      (node (ref "Q1") (pin "2") (pinfunction "SOURCE_2") (pintype "passive"))
      (node (ref "R5") (pin "2") (pinfunction "2_2") (pintype "passive"))
      (node (ref "U1") (pin "2") (pinfunction "VCC_2") (pintype "passive"))
      (node (ref "U10") (pin "7") (pinfunction "IN_7") (pintype "passive"))
      (node (ref "U4") (pin "1") (pinfunction "EN_1") (pintype "passive"))
      (node (ref "U4") (pin "4") (pinfunction "VIN_4") (pintype "passive"))
      (node (ref "U6") (pin "86") (pinfunction "V5_LDO_86") (pintype "passive"))
      (node (ref "U9") (pin "7") (pinfunction "IN_7") (pintype "passive"))
    )
    (net (code "79") (name "VD12") (class "Default")
      (node (ref "C11") (pin "2") (pinfunction "2_2") (pintype "passive"))
      (node (ref "C21") (pin "2") (pinfunction "2_2") (pintype "passive"))
      (node (ref "C22") (pin "2") (pinfunction "2_2") (pintype "passive"))
      (node (ref "C23") (pin "2") (pinfunction "2_2") (pintype "passive"))
      (node (ref "C24") (pin "2") (pinfunction "2_2") (pintype "passive"))
      (node (ref "C31") (pin "1") (pinfunction "1_1") (pintype "passive"))
      (node (ref "C32") (pin "2") (pinfunction "2_2") (pintype "passive"))
      (node (ref "C33") (pin "2") (pinfunction "2_2") (pintype "passive"))
      (node (ref "C9") (pin "2") (pinfunction "2_2") (pintype "passive"))
      (node (ref "LB4") (pin "2") (pinfunction "2_2") (pintype "passive"))
      (node (ref "R8") (pin "1") (pinfunction "1_1") (pintype "passive"))
      (node (ref "U6") (pin "14") (pinfunction "VD12_14") (pintype "passive"))
      (node (ref "U6") (pin "15") (pinfunction "VD12_15") (pintype "passive"))
      (node (ref "U6") (pin "21") (pinfunction "VD12_21") (pintype "passive"))
      (node (ref "U6") (pin "23") (pinfunction "VD12_23") (pintype "passive"))
      (node (ref "U6") (pin "29") (pinfunction "VD12_29") (pintype "passive"))
      (node (ref "U6") (pin "30") (pinfunction "VD12_30") (pintype "passive"))
      (node (ref "U6") (pin "36") (pinfunction "VD12_36") (pintype "passive"))
      (node (ref "U6") (pin "37") (pinfunction "VD12_37") (pintype "passive"))
      (node (ref "U6") (pin "43") (pinfunction "VD12_43") (pintype "passive"))
      (node (ref "U6") (pin "44") (pinfunction "DVDD12_44") (pintype "passive"))
      (node (ref "U6") (pin "49") (pinfunction "DVDD12_49") (pintype "passive"))
      (node (ref "U6") (pin "57") (pinfunction "DVDD12_57") (pintype "passive"))
      (node (ref "U6") (pin "75") (pinfunction "DVDD12_75") (pintype "passive"))
    )
    (net (code "80") (name "VD33") (class "Default")
      (node (ref "C15") (pin "1") (pinfunction "1_1") (pintype "passive"))
      (node (ref "C20") (pin "2") (pinfunction "2_2") (pintype "passive"))
      (node (ref "R14") (pin "1") (pinfunction "1_1") (pintype "passive"))
      (node (ref "R15") (pin "2") (pinfunction "2_2") (pintype "passive"))
      (node (ref "R16") (pin "1") (pinfunction "1_1") (pintype "passive"))
      (node (ref "R17") (pin "1") (pinfunction "1_1") (pintype "passive"))
      (node (ref "R18") (pin "1") (pinfunction "1_1") (pintype "passive"))
      (node (ref "R19") (pin "1") (pinfunction "1_1") (pintype "passive"))
      (node (ref "R20") (pin "1") (pinfunction "1_1") (pintype "passive"))
      (node (ref "R21") (pin "1") (pinfunction "1_1") (pintype "passive"))
      (node (ref "R22") (pin "1") (pinfunction "1_1") (pintype "passive"))
      (node (ref "R23") (pin "1") (pinfunction "1_1") (pintype "passive"))
      (node (ref "U6") (pin "58") (pinfunction "DVDD_58") (pintype "passive"))
      (node (ref "U6") (pin "63") (pinfunction "AVDD_63") (pintype "passive"))
      (node (ref "U6") (pin "66") (pinfunction "AVDD_66") (pintype "passive"))
      (node (ref "U6") (pin "70") (pinfunction "AVDD_70") (pintype "passive"))
      (node (ref "U6") (pin "73") (pinfunction "DVDD_73") (pintype "passive"))
      (node (ref "U6") (pin "85") (pinfunction "V33_OUT_85") (pintype "passive"))
      (node (ref "U8") (pin "8") (pinfunction "VCC_8") (pintype "passive"))
    )
    (net (code "81") (name "VDP1") (class "Default")
      (node (ref "C12") (pin "1") (pinfunction "1_1") (pintype "passive"))
      (node (ref "C13") (pin "2") (pinfunction "2_2") (pintype "passive"))
      (node (ref "DOWN1") (pin "1") (pinfunction "VCC_1") (pintype "power_in"))
      (node (ref "U2") (pin "2") (pinfunction "VCC_2") (pintype "passive"))
      (node (ref "U9") (pin "8") (pinfunction "OUTA_8") (pintype "passive"))
    )
    (net (code "82") (name "VDP2") (class "Default")
      (node (ref "C25") (pin "1") (pinfunction "1_1") (pintype "passive"))
      (node (ref "C26") (pin "2") (pinfunction "2_2") (pintype "passive"))
      (node (ref "DOWN2") (pin "1") (pinfunction "VCC_1") (pintype "power_in"))
      (node (ref "U3") (pin "2") (pinfunction "VCC_2") (pintype "passive"))
      (node (ref "U9") (pin "5") (pinfunction "OUTB_5") (pintype "passive"))
    )
    (net (code "83") (name "VDP3") (class "Default")
      (node (ref "C34") (pin "1") (pinfunction "1_1") (pintype "passive"))
      (node (ref "C35") (pin "2") (pinfunction "2_2") (pintype "passive"))
      (node (ref "DOWN3") (pin "1") (pinfunction "VCC_1") (pintype "power_in"))
      (node (ref "U10") (pin "8") (pinfunction "OUTA_8") (pintype "passive"))
      (node (ref "U5") (pin "2") (pinfunction "VCC_2") (pintype "passive"))
    )
    (net (code "84") (name "VDP4") (class "Default")
      (node (ref "C36") (pin "1") (pinfunction "1_1") (pintype "passive"))
      (node (ref "C37") (pin "2") (pinfunction "2_2") (pintype "passive"))
      (node (ref "DOWN4") (pin "1") (pinfunction "VCC_1") (pintype "power_in"))
      (node (ref "U10") (pin "5") (pinfunction "OUTB_5") (pintype "passive"))
      (node (ref "U7") (pin "2") (pinfunction "VCC_2") (pintype "passive"))
    )
    (net (code "85") (name "VMAIN") (class "Default")
      (node (ref "C1") (pin "1") (pinfunction "1_1") (pintype "passive"))
      (node (ref "C3") (pin "2") (pinfunction "2_2") (pintype "passive"))
      (node (ref "F1") (pin "1") (pinfunction "1_1") (pintype "passive"))
      (node (ref "Q1") (pin "3") (pinfunction "DRAIN_3") (pintype "passive"))
      (node (ref "U6") (pin "55") (pinfunction "VBUS_55") (pintype "passive"))
    )
    (net (code "86") (name "unconnected-(U1-NC-Pad3)") (class "Default")
      (node (ref "U1") (pin "3") (pinfunction "NC_3") (pintype "passive+no_connect"))
    )
    (net (code "87") (name "unconnected-(U1-NC-Pad8)") (class "Default")
      (node (ref "U1") (pin "8") (pinfunction "NC_8") (pintype "passive+no_connect"))
    )
    (net (code "88") (name "unconnected-(U2-NC-Pad3)") (class "Default")
      (node (ref "U2") (pin "3") (pinfunction "NC_3") (pintype "passive+no_connect"))
    )
    (net (code "89") (name "unconnected-(U2-NC-Pad8)") (class "Default")
      (node (ref "U2") (pin "8") (pinfunction "NC_8") (pintype "passive+no_connect"))
    )
    (net (code "90") (name "unconnected-(U3-NC-Pad3)") (class "Default")
      (node (ref "U3") (pin "3") (pinfunction "NC_3") (pintype "passive+no_connect"))
    )
    (net (code "91") (name "unconnected-(U3-NC-Pad8)") (class "Default")
      (node (ref "U3") (pin "8") (pinfunction "NC_8") (pintype "passive+no_connect"))
    )
    (net (code "92") (name "unconnected-(U5-NC-Pad3)") (class "Default")
      (node (ref "U5") (pin "3") (pinfunction "NC_3") (pintype "passive+no_connect"))
    )
    (net (code "93") (name "unconnected-(U5-NC-Pad8)") (class "Default")
      (node (ref "U5") (pin "8") (pinfunction "NC_8") (pintype "passive+no_connect"))
    )
    (net (code "94") (name "unconnected-(U6-NC-Pad4)") (class "Default")
      (node (ref "U6") (pin "4") (pinfunction "NC_4") (pintype "passive+no_connect"))
    )
    (net (code "95") (name "unconnected-(U6-NC-Pad5)") (class "Default")
      (node (ref "U6") (pin "5") (pinfunction "NC_5") (pintype "passive+no_connect"))
    )
    (net (code "96") (name "unconnected-(U6-NC-Pad8)") (class "Default")
      (node (ref "U6") (pin "8") (pinfunction "NC_8") (pintype "passive+no_connect"))
    )
    (net (code "97") (name "unconnected-(U6-NC-Pad22)") (class "Default")
      (node (ref "U6") (pin "22") (pinfunction "NC_22") (pintype "passive"))
    )
    (net (code "98") (name "unconnected-(U6-PAMBER1-Pad52)") (class "Default")
      (node (ref "U6") (pin "52") (pinfunction "PAMBER1_52") (pintype "passive+no_connect"))
    )
    (net (code "99") (name "unconnected-(U6-PAMBER2-Pad87)") (class "Default")
      (node (ref "U6") (pin "87") (pinfunction "PAMBER2_87") (pintype "passive+no_connect"))
    )
    (net (code "100") (name "unconnected-(U6-PAMBER3-Pad56)") (class "Default")
      (node (ref "U6") (pin "56") (pinfunction "PAMBER3_56") (pintype "passive+no_connect"))
    )
    (net (code "101") (name "unconnected-(U6-PAMBER4-Pad1)") (class "Default")
      (node (ref "U6") (pin "1") (pinfunction "PAMBER4_1") (pintype "passive+no_connect"))
    )
    (net (code "102") (name "unconnected-(U6-TEST-Pad76)") (class "Default")
      (node (ref "U6") (pin "76") (pinfunction "TEST_76") (pintype "passive+no_connect"))
    )
    (net (code "103") (name "unconnected-(U7-NC-Pad3)") (class "Default")
      (node (ref "U7") (pin "3") (pinfunction "NC_3") (pintype "passive+no_connect"))
    )
    (net (code "104") (name "unconnected-(U7-NC-Pad8)") (class "Default")
      (node (ref "U7") (pin "8") (pinfunction "NC_8") (pintype "passive+no_connect"))
    )
    (net (code "105") (name "unconnected-(USB1-SBU1-PadA8)") (class "Default")
      (node (ref "USB1") (pin "A8") (pinfunction "SBU1_A8") (pintype "passive+no_connect"))
    )
    (net (code "106") (name "unconnected-(USB1-SBU2-PadB8)") (class "Default")
      (node (ref "USB1") (pin "B8") (pinfunction "SBU2_B8") (pintype "passive+no_connect"))
    )
    (net (code "107") (name "unconnected-(USB2-CC1-PadA5)") (class "Default")
      (node (ref "USB2") (pin "A5") (pinfunction "CC1_A5") (pintype "passive+no_connect"))
    )
    (net (code "108") (name "unconnected-(USB2-CC2-PadB5)") (class "Default")
      (node (ref "USB2") (pin "B5") (pinfunction "CC2_B5") (pintype "passive+no_connect"))
    )
  )
)
